# MCU.net
KiCad netlist of a schematic drawn in Altium Designer
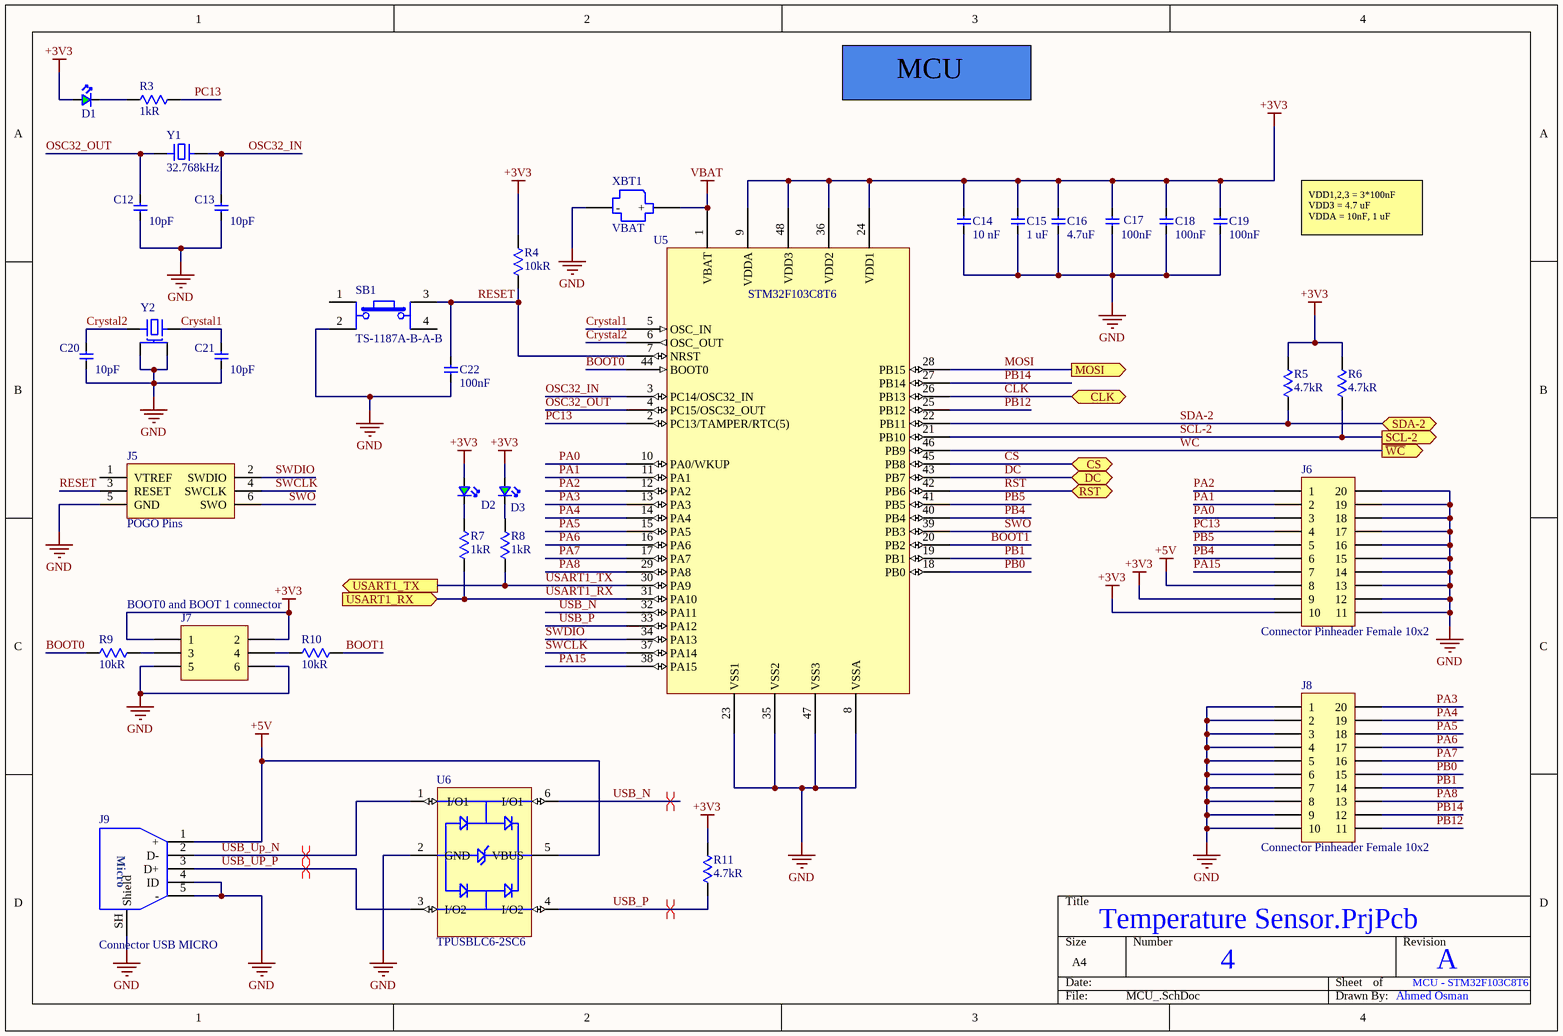
[diagram p0: MCU_.SchDoc]

(export (version "E")
  (design (tool "Eeschema 10.0.6"))
  (components
    (comp (ref "C12")
      (value "10pF")
      (footprint "CAP 0603")
      (description "10 pF ±5% 50V Ceramic Capacitor C0G, NP0 0603 (1608 Metric)")
      (fields (field (name "TOLERANCE") "5%") (field (name "VOLTAGE") "50V"))
      (libsource (lib "Temperature project symbols") (part "CAP  0603 10 pF ±5% 50V"))
    )
    (comp (ref "C13")
      (value "10pF")
      (footprint "CAP 0603")
      (description "10 pF ±5% 50V Ceramic Capacitor C0G, NP0 0603 (1608 Metric)")
      (fields (field (name "TOLERANCE") "5%") (field (name "VOLTAGE") "50V"))
      (libsource (lib "Temperature project symbols") (part "CAP  0603 10 pF ±5% 50V"))
    )
    (comp (ref "C14")
      (value "10 nF")
      (footprint "CAP 0603")
      (description "10000 pF ±10% 25V Ceramic Capacitor X7R 0603 (1608 Metric)")
      (libsource (lib "Temperature project symbols") (part "CAP  0603 10 nF ±10% 25V"))
    )
    (comp (ref "C15")
      (value "1 uF")
      (footprint "CAP 0603")
      (description "1 µF ±10% 25V Ceramic Capacitor X5R 0603 (1608 Metric)")
      (fields (field (name "MANUFACTURER") "Yageo") (field (name "TOLERANCE") "10%"))
      (libsource (lib "Temperature project symbols") (part "CAP  0603 1 µF ±10% 25V"))
    )
    (comp (ref "C16")
      (value "4.7uF")
      (footprint "CAP 0603")
      (description "4.7 µF ±10% 35V Ceramic Capacitor X5R 0603 (1608 Metric)")
      (fields (field (name "TOLERANCE") "10%") (field (name "VOLTAGE") "35V"))
      (libsource (lib "Temperature project symbols") (part "CAP  0603 4.7 µF ±10% 35V"))
    )
    (comp (ref "C17")
      (value "100nF")
      (footprint "CAP 0603")
      (description "0.1 µF ±10% 50V Ceramic Capacitor X7R 0603 (1608 Metric)")
      (fields (field (name "TOLERANCE") "10%") (field (name "VOLTAGE") "50V"))
      (libsource (lib "Temperature project symbols") (part "CAP  0603 100nF 10% 50 V"))
    )
    (comp (ref "C18")
      (value "100nF")
      (footprint "CAP 0603")
      (description "0.1 µF ±10% 50V Ceramic Capacitor X7R 0603 (1608 Metric)")
      (fields (field (name "TOLERANCE") "10%") (field (name "VOLTAGE") "50V"))
      (libsource (lib "Temperature project symbols") (part "CAP  0603 100nF 10% 50 V"))
    )
    (comp (ref "C19")
      (value "100nF")
      (footprint "CAP 0603")
      (description "0.1 µF ±10% 50V Ceramic Capacitor X7R 0603 (1608 Metric)")
      (fields (field (name "TOLERANCE") "10%") (field (name "VOLTAGE") "50V"))
      (libsource (lib "") (part "CAP  0603 100nF 10% 50 V_1"))
    )
    (comp (ref "C20")
      (value "10pF")
      (footprint "CAP 0603")
      (description "10 pF ±5% 50V Ceramic Capacitor C0G, NP0 0603 (1608 Metric)")
      (fields (field (name "TOLERANCE") "5%") (field (name "VOLTAGE") "50V"))
      (libsource (lib "Temperature project symbols") (part "CAP  0603 10 pF ±5% 50V"))
    )
    (comp (ref "C21")
      (value "10pF")
      (footprint "CAP 0603")
      (description "10 pF ±5% 50V Ceramic Capacitor C0G, NP0 0603 (1608 Metric)")
      (fields (field (name "TOLERANCE") "5%") (field (name "VOLTAGE") "50V"))
      (libsource (lib "Temperature project symbols") (part "CAP  0603 10 pF ±5% 50V"))
    )
    (comp (ref "C22")
      (value "100nF")
      (footprint "CAP 0603")
      (description "0.1 µF ±10% 50V Ceramic Capacitor X7R 0603 (1608 Metric)")
      (fields (field (name "TOLERANCE") "10%") (field (name "VOLTAGE") "50V"))
      (libsource (lib "Temperature project symbols") (part "CAP  0603 100 nF 10% 50 V"))
    )
    (comp (ref "D1")
      (value "LED GREEN")
      (footprint "LED GREEN")
      (description "Green 520nm LED Indication - Discrete 3.2V 0603 (1608 Metric)")
      (libsource (lib "Temperature project symbols") (part "LED GREEN"))
    )
    (comp (ref "D2")
      (value "LED GREEN")
      (footprint "LED GREEN")
      (description "Green 520nm LED Indication - Discrete 3.2V 0603 (1608 Metric)")
      (libsource (lib "Temperature project symbols") (part "LED GREEN"))
    )
    (comp (ref "D3")
      (value "LED GREEN")
      (footprint "LED GREEN")
      (description "Green 520nm LED Indication - Discrete 3.2V 0603 (1608 Metric)")
      (libsource (lib "Temperature project symbols") (part "LED GREEN"))
    )
    (comp (ref "J5")
      (value "POGO Pins")
      (footprint "SEGGER_8.06.16_J-LINK_6-PIN_NEEDLE_ADAPTER")
      (description "Plug-Of-Nails™ Cable Assembly")
      (libsource (lib "Temperature project symbols") (part "POGO Pins"))
    )
    (comp (ref "J6")
      (value "Connector Pinheader Female 10x2")
      (footprint "Connector Pinheader 10x2")
      (description "20 Position Header Connector 0.100\" (2.54mm) Through Hole Gold")
      (fields (field (name "MANUFACTURER") "Sullins"))
      (libsource (lib "Temperature project symbols") (part "Connector Pinheader Female 10x2"))
    )
    (comp (ref "J7")
      (value "BOOT0 and BOOT 1 connector")
      (footprint "2X3 Female Pin Header Connector")
      (libsource (lib "Temperature project symbols") (part "BOOT0 and BOOT 1 connector"))
    )
    (comp (ref "J8")
      (value "Connector Pinheader Female 10x2")
      (footprint "Connector Pinheader 10x2")
      (description "20 Position Header Connector 0.100\" (2.54mm) Through Hole Gold")
      (fields (field (name "MANUFACTURER") "Sullins"))
      (libsource (lib "Temperature project symbols") (part "Connector Pinheader Female 10x2"))
    )
    (comp (ref "J9")
      (value "Connector USB MICRO")
      (footprint "Connector USB MICRO")
      (description "1.8A USB 2.0 1 Horizontal attachment 5P Mother -20℃~+85℃ Micro-B SMD USB Connectors ROHS")
      (libsource (lib "Temperature project symbols") (part "Connector USB MICRO"))
    )
    (comp (ref "R3")
      (value "1kR")
      (footprint "RES 0603")
      (description "1 kOhms ±1% 0.1W, 1/10W Chip Resistor 0603 (1608 Metric) Moisture Resistant Thick Film")
      (fields (field (name "MANUFACTURER") "Yageo") (field (name "TOLERANCE") "1%"))
      (libsource (lib "Temperature project symbols") (part "RES  0603 1kR ±1% 0.1W"))
    )
    (comp (ref "R4")
      (value "10kR")
      (footprint "RES 0603")
      (description "10 kOhms ±1% 0.1W, 1/10W Chip Resistor 0603 (1608 Metric) Moisture Resistant Thick Film")
      (fields (field (name "TOLERANCE") "1%"))
      (libsource (lib "Temperature project symbols") (part "RES  0603 10KR ±1% 0.1W, 1/10W"))
    )
    (comp (ref "R5")
      (value "4.7kR")
      (footprint "RES 0603")
      (description "4.7 kOhms ±1% 0.1W, 1/10W Chip Resistor 0603 (1608 Metric) Moisture Resistant Thick Film")
      (fields (field (name "TOLERANCE") "1%"))
      (libsource (lib "Temperature project symbols") (part "RES  0603 4.7 kOhms ±1% 0.1W, 1/10W"))
    )
    (comp (ref "R6")
      (value "4.7kR")
      (footprint "RES 0603")
      (description "4.7 kOhms ±1% 0.1W, 1/10W Chip Resistor 0603 (1608 Metric) Moisture Resistant Thick Film")
      (fields (field (name "TOLERANCE") "1%"))
      (libsource (lib "Temperature project symbols") (part "RES  0603 4.7 kOhms ±1% 0.1W, 1/10W"))
    )
    (comp (ref "R7")
      (value "1kR")
      (footprint "RES 0603")
      (description "1 kOhms ±1% 0.1W, 1/10W Chip Resistor 0603 (1608 Metric) Moisture Resistant Thick Film")
      (fields (field (name "MANUFACTURER") "Yageo") (field (name "TOLERANCE") "1%"))
      (libsource (lib "Temperature project symbols") (part "RES  0603 1kR ±1% 0.1W"))
    )
    (comp (ref "R8")
      (value "1kR")
      (footprint "RES 0603")
      (description "1 kOhms ±1% 0.1W, 1/10W Chip Resistor 0603 (1608 Metric) Moisture Resistant Thick Film")
      (fields (field (name "MANUFACTURER") "Yageo") (field (name "TOLERANCE") "1%"))
      (libsource (lib "") (part "RES  0603 1kR ±1% 0.1W_1"))
    )
    (comp (ref "R9")
      (value "10kR")
      (footprint "RES 0603")
      (description "10 kOhms ±1% 0.1W, 1/10W Chip Resistor 0603 (1608 Metric) Moisture Resistant Thick Film")
      (fields (field (name "TOLERANCE") "1%"))
      (libsource (lib "") (part "RES  0603 10KR ±1% 0.1W, 1/10W_1"))
    )
    (comp (ref "R10")
      (value "10kR")
      (footprint "RES 0603")
      (description "10 kOhms ±1% 0.1W, 1/10W Chip Resistor 0603 (1608 Metric) Moisture Resistant Thick Film")
      (fields (field (name "TOLERANCE") "1%"))
      (libsource (lib "") (part "RES  0603 10KR ±1% 0.1W, 1/10W_1"))
    )
    (comp (ref "R11")
      (value "4.7kR")
      (footprint "RES 0603")
      (description "4.7 kOhms ±1% 0.1W, 1/10W Chip Resistor 0603 (1608 Metric) Moisture Resistant Thick Film")
      (fields (field (name "TOLERANCE") "1%"))
      (libsource (lib "Temperature project symbols") (part "RES  0603 4.7 kOhms ±1% 0.1W, 1/10W"))
    )
    (comp (ref "SB1")
      (value "TS-1187A-B-A-B")
      (footprint "Switch")
      (libsource (lib "Temperature project symbols") (part "TS-1187A-B-A-B"))
    )
    (comp (ref "U5")
      (value "STM32F103C8T6")
      (footprint "STM32F103C8T6")
      (description "ARM® Cortex®-M3 STM32F1 Microcontroller IC 32-Bit Single-Core 72MHz 64KB (64K x 8) FLASH")
      (libsource (lib "Temperature project symbols") (part "STM32F103C8T6"))
    )
    (comp (ref "U6")
      (value "TPUSBLC6-2SC6")
      (footprint "SOT-23-6")
      (description "SOT-23-6 ESD and Surge Protection (TVS/ESD) ROHS")
      (libsource (lib "Temperature project symbols") (part "TPUSBLC6-2SC6"))
    )
    (comp (ref "XBT1")
      (value "VBAT")
      (footprint "Battery Holder VBAT")
      (description "Battery holder CR2032 SMD Button And Strip Battery Connector ROHS")
      (libsource (lib "Temperature project symbols") (part "VBAT"))
    )
    (comp (ref "Y1")
      (value "32.768kHz")
      (footprint "SMD2012-2P")
      (description "32.768kHz Surface Mount Crystal 7pF ±20ppm SMD2012-2P Crystals ROHS")
      (libsource (lib "Temperature project symbols") (part "Crystal 32.768kHz"))
    )
    (comp (ref "Y2")
      (value "Crystal 10pF ±10ppm ±15ppm SMD3225")
      (footprint "SMD3225-4P")
      (description "8MHz Surface Mount Crystal 10pF ±10ppm ±15ppm SMD3225-4P Crystals ROHS")
      (libsource (lib "Temperature project symbols") (part "Crystal 10pF ±10ppm ±15ppm SMD3225"))
    )
  )
  (nets
    (net (code "1") (name "+3V3") (class "Default")
      (node (ref "C14") (pin "2") (pintype "passive"))
      (node (ref "C15") (pin "2") (pintype "passive"))
      (node (ref "C16") (pin "2") (pintype "passive"))
      (node (ref "C17") (pin "2") (pintype "passive"))
      (node (ref "C18") (pin "2") (pintype "passive"))
      (node (ref "C19") (pin "2") (pintype "passive"))
      (node (ref "D1") (pin "2") (pinfunction "2_2") (pintype "passive"))
      (node (ref "D2") (pin "2") (pinfunction "2_2") (pintype "passive"))
      (node (ref "D3") (pin "2") (pinfunction "2_2") (pintype "passive"))
      (node (ref "J6") (pin "10") (pinfunction "10_10") (pintype "passive"))
      (node (ref "J6") (pin "9") (pinfunction "9_9") (pintype "passive"))
      (node (ref "J7") (pin "1") (pinfunction "1_1") (pintype "passive"))
      (node (ref "J7") (pin "2") (pinfunction "2_2") (pintype "passive"))
      (node (ref "R11") (pin "2") (pinfunction "2_2") (pintype "passive"))
      (node (ref "R4") (pin "2") (pinfunction "2_2") (pintype "passive"))
      (node (ref "R5") (pin "2") (pinfunction "2_2") (pintype "passive"))
      (node (ref "R6") (pin "2") (pinfunction "2_2") (pintype "passive"))
      (node (ref "U5") (pin "24") (pinfunction "VDD1_24") (pintype "power_in"))
      (node (ref "U5") (pin "36") (pinfunction "VDD2_36") (pintype "power_in"))
      (node (ref "U5") (pin "48") (pinfunction "VDD3_48") (pintype "power_in"))
      (node (ref "U5") (pin "9") (pinfunction "VDDA_9") (pintype "power_in"))
    )
    (net (code "2") (name "+5V") (class "Default")
      (node (ref "J6") (pin "8") (pinfunction "8_8") (pintype "passive"))
      (node (ref "J9") (pin "1") (pinfunction "+_1") (pintype "passive"))
      (node (ref "U6") (pin "5") (pinfunction "VBUS_5") (pintype "passive"))
    )
    (net (code "3") (name "/BOOT0") (class "Default")
      (node (ref "R9") (pin "1") (pinfunction "1_1") (pintype "passive"))
      (node (ref "U5") (pin "44") (pinfunction "BOOT0_44") (pintype "input"))
    )
    (net (code "4") (name "/BOOT1") (class "Default")
      (node (ref "R10") (pin "2") (pinfunction "2_2") (pintype "passive"))
      (node (ref "U5") (pin "20") (pinfunction "PB2_20") (pintype "bidirectional"))
    )
    (net (code "5") (name "/CLK") (class "Default")
      (node (ref "U5") (pin "26") (pinfunction "PB13_26") (pintype "bidirectional"))
    )
    (net (code "6") (name "/CS") (class "Default")
      (node (ref "U5") (pin "45") (pinfunction "PB8_45") (pintype "bidirectional"))
    )
    (net (code "7") (name "/Crystal1") (class "Default")
      (node (ref "C21") (pin "2") (pintype "passive"))
      (node (ref "U5") (pin "5") (pinfunction "OSC_IN_5") (pintype "input"))
      (node (ref "Y2") (pin "3") (pinfunction "3_3") (pintype "passive"))
    )
    (net (code "8") (name "/Crystal2") (class "Default")
      (node (ref "C20") (pin "2") (pintype "passive"))
      (node (ref "U5") (pin "6") (pinfunction "OSC_OUT_6") (pintype "output"))
      (node (ref "Y2") (pin "1") (pinfunction "1_1") (pintype "passive"))
    )
    (net (code "9") (name "/DC") (class "Default")
      (node (ref "U5") (pin "43") (pinfunction "PB7_43") (pintype "bidirectional"))
    )
    (net (code "10") (name "/MOSI") (class "Default")
      (node (ref "U5") (pin "28") (pinfunction "PB15_28") (pintype "bidirectional"))
    )
    (net (code "11") (name "/OSC32_IN") (class "Default")
      (node (ref "C13") (pin "2") (pintype "passive"))
      (node (ref "U5") (pin "3") (pinfunction "PC14/OSC32_IN_3") (pintype "bidirectional"))
      (node (ref "Y1") (pin "2") (pinfunction "2_2") (pintype "passive"))
    )
    (net (code "12") (name "/OSC32_OUT") (class "Default")
      (node (ref "C12") (pin "2") (pintype "passive"))
      (node (ref "U5") (pin "4") (pinfunction "PC15/OSC32_OUT_4") (pintype "bidirectional"))
      (node (ref "Y1") (pin "1") (pinfunction "1_1") (pintype "passive"))
    )
    (net (code "13") (name "/PA0") (class "Default")
      (node (ref "J6") (pin "3") (pinfunction "3_3") (pintype "passive"))
      (node (ref "U5") (pin "10") (pinfunction "PA0/WKUP_10") (pintype "bidirectional"))
    )
    (net (code "14") (name "/PA1") (class "Default")
      (node (ref "J6") (pin "2") (pinfunction "2_2") (pintype "passive"))
      (node (ref "U5") (pin "11") (pinfunction "PA1_11") (pintype "bidirectional"))
    )
    (net (code "15") (name "/PA2") (class "Default")
      (node (ref "J6") (pin "1") (pinfunction "1_1") (pintype "passive"))
      (node (ref "U5") (pin "12") (pinfunction "PA2_12") (pintype "bidirectional"))
    )
    (net (code "16") (name "/PA3") (class "Default")
      (node (ref "J8") (pin "20") (pinfunction "20_20") (pintype "passive"))
      (node (ref "U5") (pin "13") (pinfunction "PA3_13") (pintype "bidirectional"))
    )
    (net (code "17") (name "/PA4") (class "Default")
      (node (ref "J8") (pin "19") (pinfunction "19_19") (pintype "passive"))
      (node (ref "U5") (pin "14") (pinfunction "PA4_14") (pintype "bidirectional"))
    )
    (net (code "18") (name "/PA5") (class "Default")
      (node (ref "J8") (pin "18") (pinfunction "18_18") (pintype "passive"))
      (node (ref "U5") (pin "15") (pinfunction "PA5_15") (pintype "bidirectional"))
    )
    (net (code "19") (name "/PA6") (class "Default")
      (node (ref "J8") (pin "17") (pinfunction "17_17") (pintype "passive"))
      (node (ref "U5") (pin "16") (pinfunction "PA6_16") (pintype "bidirectional"))
    )
    (net (code "20") (name "/PA7") (class "Default")
      (node (ref "J8") (pin "16") (pinfunction "16_16") (pintype "passive"))
      (node (ref "U5") (pin "17") (pinfunction "PA7_17") (pintype "bidirectional"))
    )
    (net (code "21") (name "/PA8") (class "Default")
      (node (ref "J8") (pin "13") (pinfunction "13_13") (pintype "passive"))
      (node (ref "U5") (pin "29") (pinfunction "PA8_29") (pintype "bidirectional"))
    )
    (net (code "22") (name "/PA15") (class "Default")
      (node (ref "J6") (pin "7") (pinfunction "7_7") (pintype "passive"))
      (node (ref "U5") (pin "38") (pinfunction "PA15_38") (pintype "bidirectional"))
    )
    (net (code "23") (name "/PB0") (class "Default")
      (node (ref "J8") (pin "15") (pinfunction "15_15") (pintype "passive"))
      (node (ref "U5") (pin "18") (pinfunction "PB0_18") (pintype "bidirectional"))
    )
    (net (code "24") (name "/PB1") (class "Default")
      (node (ref "J8") (pin "14") (pinfunction "14_14") (pintype "passive"))
      (node (ref "U5") (pin "19") (pinfunction "PB1_19") (pintype "bidirectional"))
    )
    (net (code "25") (name "/PB4") (class "Default")
      (node (ref "J6") (pin "6") (pinfunction "6_6") (pintype "passive"))
      (node (ref "U5") (pin "40") (pinfunction "PB4_40") (pintype "bidirectional"))
    )
    (net (code "26") (name "/PB5") (class "Default")
      (node (ref "J6") (pin "5") (pinfunction "5_5") (pintype "passive"))
      (node (ref "U5") (pin "41") (pinfunction "PB5_41") (pintype "bidirectional"))
    )
    (net (code "27") (name "/PB12") (class "Default")
      (node (ref "J8") (pin "11") (pinfunction "11_11") (pintype "passive"))
      (node (ref "U5") (pin "25") (pinfunction "PB12_25") (pintype "bidirectional"))
    )
    (net (code "28") (name "/PB14") (class "Default")
      (node (ref "J8") (pin "12") (pinfunction "12_12") (pintype "passive"))
      (node (ref "U5") (pin "27") (pinfunction "PB14_27") (pintype "bidirectional"))
    )
    (net (code "29") (name "/PC13") (class "Default")
      (node (ref "J6") (pin "4") (pinfunction "4_4") (pintype "passive"))
      (node (ref "R3") (pin "2") (pinfunction "2_2") (pintype "passive"))
      (node (ref "U5") (pin "2") (pinfunction "PC13/TAMPER/RTC(5)_2") (pintype "bidirectional"))
    )
    (net (code "30") (name "/RESET") (class "Default")
      (node (ref "C22") (pin "2") (pintype "passive"))
      (node (ref "J5") (pin "3") (pinfunction "RESET_3") (pintype "passive"))
      (node (ref "R4") (pin "1") (pinfunction "1_1") (pintype "passive"))
      (node (ref "SB1") (pin "3") (pinfunction "3_3") (pintype "passive"))
      (node (ref "U5") (pin "7") (pinfunction "NRST_7") (pintype "bidirectional"))
    )
    (net (code "31") (name "/RST") (class "Default")
      (node (ref "U5") (pin "42") (pinfunction "PB6_42") (pintype "bidirectional"))
    )
    (net (code "32") (name "/SCL-2") (class "Default")
      (node (ref "R6") (pin "1") (pinfunction "1_1") (pintype "passive"))
      (node (ref "U5") (pin "21") (pinfunction "PB10_21") (pintype "bidirectional"))
    )
    (net (code "33") (name "/SDA-2") (class "Default")
      (node (ref "R5") (pin "1") (pinfunction "1_1") (pintype "passive"))
      (node (ref "U5") (pin "22") (pinfunction "PB11_22") (pintype "bidirectional"))
    )
    (net (code "34") (name "/SWCLK") (class "Default")
      (node (ref "J5") (pin "4") (pinfunction "SWCLK_4") (pintype "passive"))
      (node (ref "U5") (pin "37") (pinfunction "PA14_37") (pintype "bidirectional"))
    )
    (net (code "35") (name "/SWDIO") (class "Default")
      (node (ref "J5") (pin "2") (pinfunction "SWDIO_2") (pintype "passive"))
      (node (ref "U5") (pin "34") (pinfunction "PA13_34") (pintype "bidirectional"))
    )
    (net (code "36") (name "/SWO") (class "Default")
      (node (ref "J5") (pin "6") (pinfunction "SWO_6") (pintype "passive"))
      (node (ref "U5") (pin "39") (pinfunction "PB3_39") (pintype "bidirectional"))
    )
    (net (code "37") (name "/USART1_RX") (class "Default")
      (node (ref "R7") (pin "1") (pinfunction "1_1") (pintype "passive"))
      (node (ref "U5") (pin "31") (pinfunction "PA10_31") (pintype "bidirectional"))
    )
    (net (code "38") (name "/USART1_TX") (class "Default")
      (node (ref "R8") (pin "1") (pinfunction "1_1") (pintype "passive"))
      (node (ref "U5") (pin "30") (pinfunction "PA9_30") (pintype "bidirectional"))
    )
    (net (code "39") (name "/USB_N") (class "Default")
      (node (ref "U5") (pin "32") (pinfunction "PA11_32") (pintype "bidirectional"))
      (node (ref "U6") (pin "6") (pinfunction "I/O1_6") (pintype "bidirectional"))
    )
    (net (code "40") (name "/USB_P") (class "Default")
      (node (ref "R11") (pin "1") (pinfunction "1_1") (pintype "passive"))
      (node (ref "U5") (pin "33") (pinfunction "PA12_33") (pintype "bidirectional"))
      (node (ref "U6") (pin "4") (pinfunction "I/O2_4") (pintype "bidirectional"))
    )
    (net (code "41") (name "/USB_UP_P") (class "Default")
      (node (ref "J9") (pin "3") (pinfunction "D+_3") (pintype "passive"))
      (node (ref "U6") (pin "3") (pinfunction "I/O2_3") (pintype "bidirectional"))
    )
    (net (code "42") (name "/USB_Up_N") (class "Default")
      (node (ref "J9") (pin "2") (pinfunction "D-_2") (pintype "passive"))
      (node (ref "U6") (pin "1") (pinfunction "I/O1_1") (pintype "bidirectional"))
    )
    (net (code "43") (name "/~{WC}") (class "Default")
      (node (ref "U5") (pin "46") (pinfunction "PB9_46") (pintype "bidirectional"))
    )
    (net (code "44") (name "GND") (class "Default")
      (node (ref "C12") (pin "1") (pintype "passive"))
      (node (ref "C13") (pin "1") (pintype "passive"))
      (node (ref "C14") (pin "1") (pintype "passive"))
      (node (ref "C15") (pin "1") (pintype "passive"))
      (node (ref "C16") (pin "1") (pintype "passive"))
      (node (ref "C17") (pin "1") (pintype "passive"))
      (node (ref "C18") (pin "1") (pintype "passive"))
      (node (ref "C19") (pin "1") (pintype "passive"))
      (node (ref "C20") (pin "1") (pintype "passive"))
      (node (ref "C21") (pin "1") (pintype "passive"))
      (node (ref "C22") (pin "1") (pintype "passive"))
      (node (ref "J5") (pin "5") (pinfunction "GND_5") (pintype "passive"))
      (node (ref "J6") (pin "11") (pinfunction "11_11") (pintype "passive"))
      (node (ref "J6") (pin "12") (pinfunction "12_12") (pintype "passive"))
      (node (ref "J6") (pin "13") (pinfunction "13_13") (pintype "passive"))
      (node (ref "J6") (pin "14") (pinfunction "14_14") (pintype "passive"))
      (node (ref "J6") (pin "15") (pinfunction "15_15") (pintype "passive"))
      (node (ref "J6") (pin "16") (pinfunction "16_16") (pintype "passive"))
      (node (ref "J6") (pin "17") (pinfunction "17_17") (pintype "passive"))
      (node (ref "J6") (pin "18") (pinfunction "18_18") (pintype "passive"))
      (node (ref "J6") (pin "19") (pinfunction "19_19") (pintype "passive"))
      (node (ref "J6") (pin "20") (pinfunction "20_20") (pintype "passive"))
      (node (ref "J7") (pin "5") (pinfunction "5_5") (pintype "passive"))
      (node (ref "J7") (pin "6") (pinfunction "6_6") (pintype "passive"))
      (node (ref "J8") (pin "1") (pinfunction "1_1") (pintype "passive"))
      (node (ref "J8") (pin "10") (pinfunction "10_10") (pintype "passive"))
      (node (ref "J8") (pin "2") (pinfunction "2_2") (pintype "passive"))
      (node (ref "J8") (pin "3") (pinfunction "3_3") (pintype "passive"))
      (node (ref "J8") (pin "4") (pinfunction "4_4") (pintype "passive"))
      (node (ref "J8") (pin "5") (pinfunction "5_5") (pintype "passive"))
      (node (ref "J8") (pin "6") (pinfunction "6_6") (pintype "passive"))
      (node (ref "J8") (pin "7") (pinfunction "7_7") (pintype "passive"))
      (node (ref "J8") (pin "8") (pinfunction "8_8") (pintype "passive"))
      (node (ref "J8") (pin "9") (pinfunction "9_9") (pintype "passive"))
      (node (ref "J9") (pin "4") (pinfunction "ID_4") (pintype "passive"))
      (node (ref "J9") (pin "5") (pinfunction "-_5") (pintype "passive"))
      (node (ref "J9") (pin "SH") (pinfunction "Shield_SH") (pintype "passive"))
      (node (ref "SB1") (pin "2") (pinfunction "2_2") (pintype "passive"))
      (node (ref "U5") (pin "23") (pinfunction "VSS1_23") (pintype "power_in"))
      (node (ref "U5") (pin "35") (pinfunction "VSS2_35") (pintype "power_in"))
      (node (ref "U5") (pin "47") (pinfunction "VSS3_47") (pintype "power_in"))
      (node (ref "U5") (pin "8") (pinfunction "VSSA_8") (pintype "power_in"))
      (node (ref "U6") (pin "2") (pinfunction "GND_2") (pintype "passive"))
      (node (ref "XBT1") (pin "1") (pinfunction "-_1") (pintype "passive"))
      (node (ref "Y2") (pin "2") (pinfunction "GND_2") (pintype "passive"))
      (node (ref "Y2") (pin "4") (pinfunction "GND_4") (pintype "passive"))
    )
    (net (code "45") (name "Net-(D1-Pad1)") (class "Default")
      (node (ref "D1") (pin "1") (pinfunction "1_1") (pintype "passive"))
      (node (ref "R3") (pin "1") (pinfunction "1_1") (pintype "passive"))
    )
    (net (code "46") (name "Net-(D2-Pad1)") (class "Default")
      (node (ref "D2") (pin "1") (pinfunction "1_1") (pintype "passive"))
      (node (ref "R7") (pin "2") (pinfunction "2_2") (pintype "passive"))
    )
    (net (code "47") (name "Net-(D3-Pad1)") (class "Default")
      (node (ref "D3") (pin "1") (pinfunction "1_1") (pintype "passive"))
      (node (ref "R8") (pin "2") (pinfunction "2_2") (pintype "passive"))
    )
    (net (code "48") (name "Net-(J7-Pad3)") (class "Default")
      (node (ref "J7") (pin "3") (pinfunction "3_3") (pintype "passive"))
      (node (ref "R9") (pin "2") (pinfunction "2_2") (pintype "passive"))
    )
    (net (code "49") (name "Net-(J7-Pad4)") (class "Default")
      (node (ref "J7") (pin "4") (pinfunction "4_4") (pintype "passive"))
      (node (ref "R10") (pin "1") (pinfunction "1_1") (pintype "passive"))
    )
    (net (code "50") (name "VBAT") (class "Default")
      (node (ref "U5") (pin "1") (pinfunction "VBAT_1") (pintype "power_in"))
      (node (ref "XBT1") (pin "2") (pinfunction "+_2") (pintype "passive"))
    )
    (net (code "51") (name "unconnected-(J5-VTREF-Pad1)") (class "Default")
      (node (ref "J5") (pin "1") (pinfunction "VTREF_1") (pintype "passive"))
    )
    (net (code "52") (name "unconnected-(SB1-Pad1)") (class "Default")
      (node (ref "SB1") (pin "1") (pinfunction "1_1") (pintype "passive"))
    )
    (net (code "53") (name "unconnected-(SB1-Pad4)") (class "Default")
      (node (ref "SB1") (pin "4") (pinfunction "4_4") (pintype "passive"))
    )
  )
)
